# Beehive_sensor_PCB_Rev_2_0_Fixed.net
KiCad netlist of a schematic drawn in EAGLE
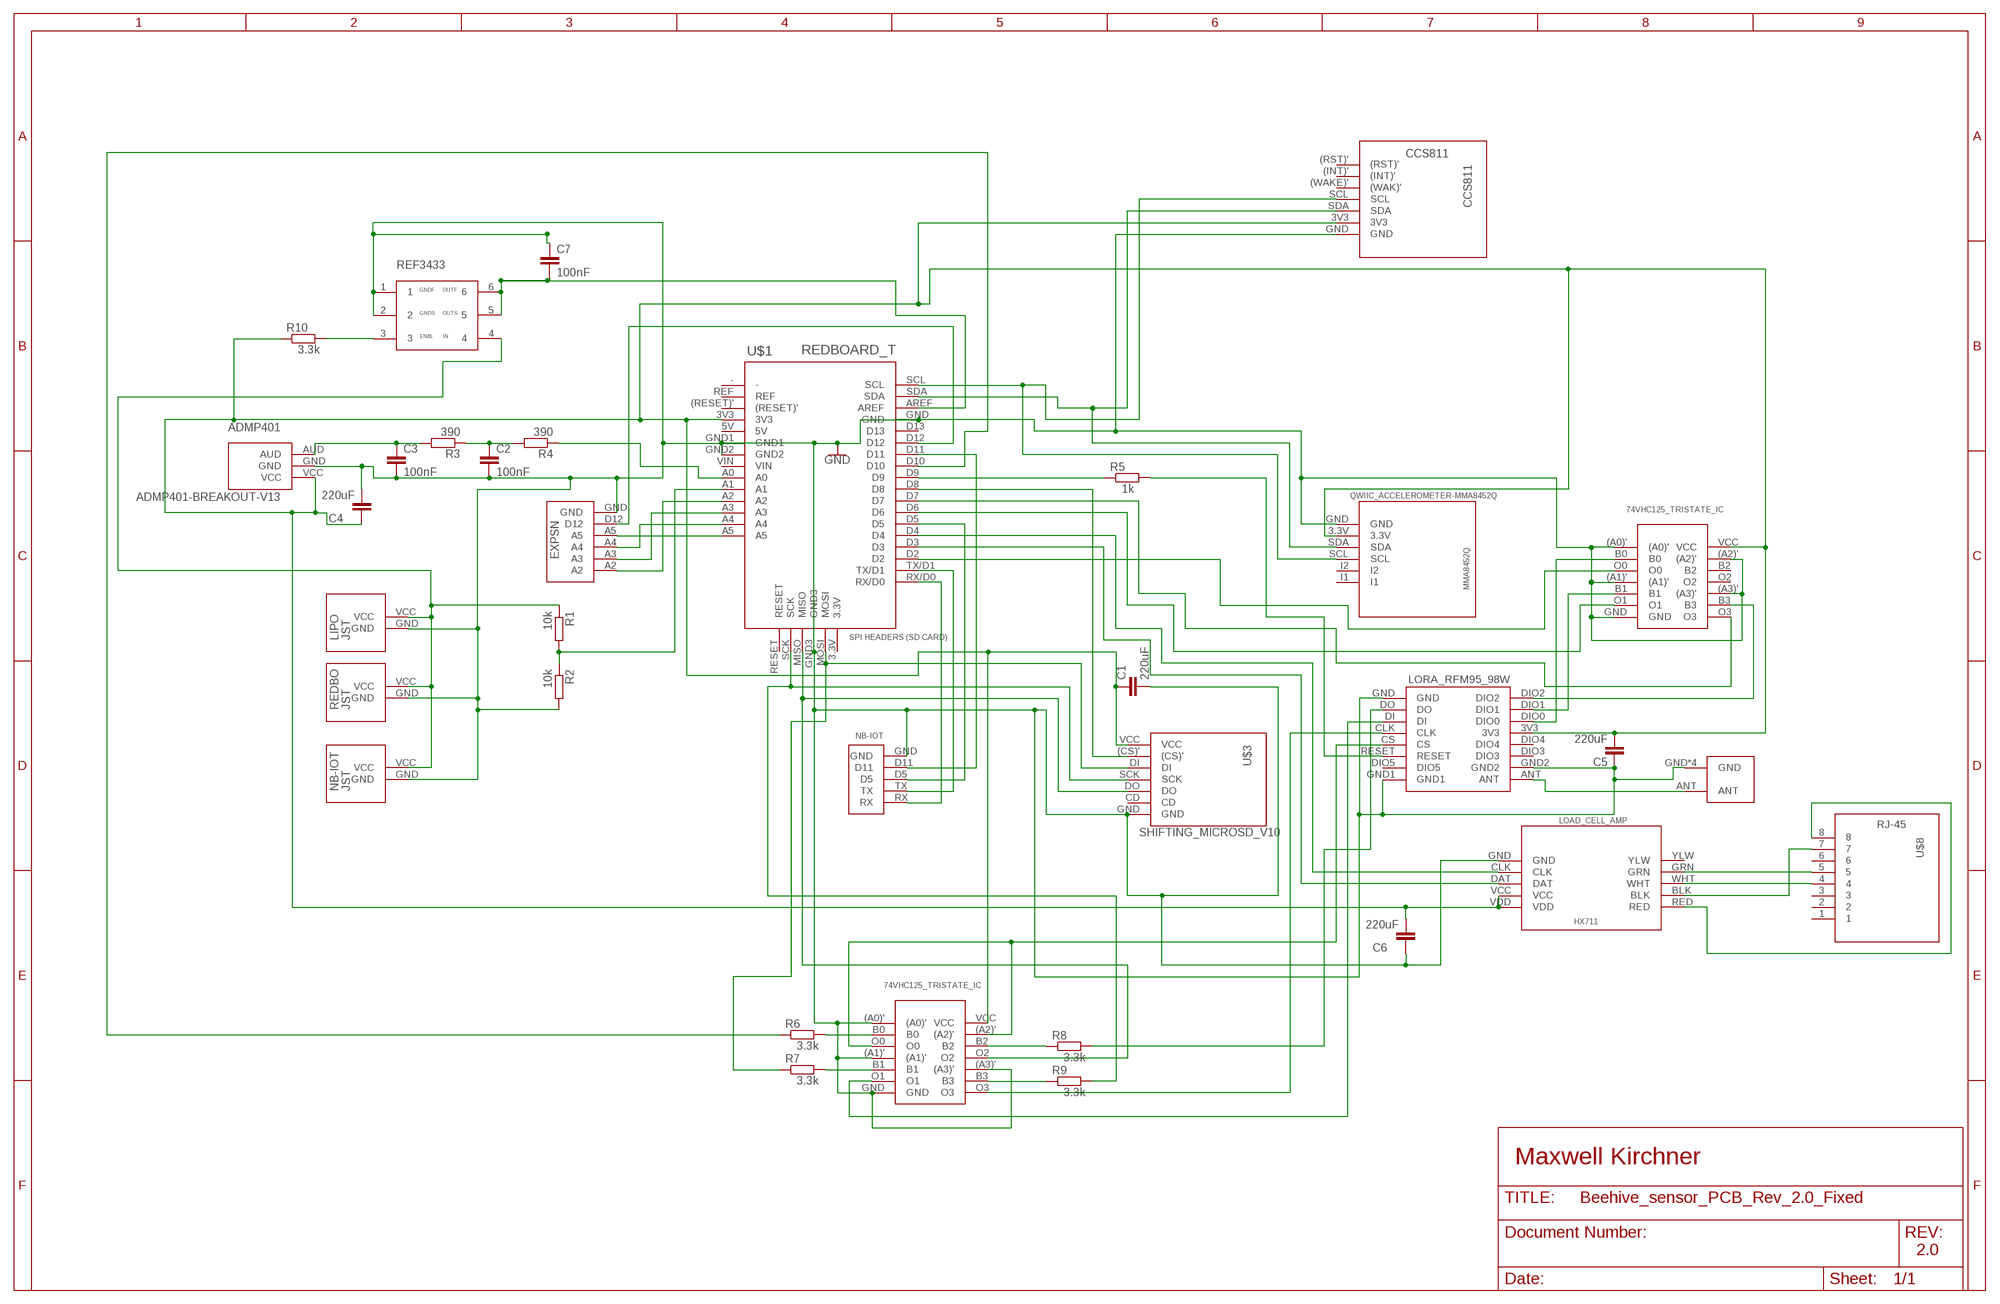
[diagram p0: schematic, sheet 1]

(export (version "E")
  (design (tool "Eeschema 10.0.6"))
  (components
    (comp (ref "ADMP401")
      (value "ADMP401-BREAKOUT-V13")
      (footprint "eagle-import:ADMP401-BREAKOUT-V13")
      (libsource (lib "eagle-import") (part "ADMP401-BREAKOUT-V13"))
    )
    (comp (ref "C1")
      (value "220uF")
      (footprint "eagle-import:C025-025X050")
      (libsource (lib "eagle-import") (part "C-EU025-025X050"))
    )
    (comp (ref "C2")
      (value "100nF")
      (footprint "eagle-import:C025-025X050")
      (libsource (lib "eagle-import") (part "C-EU025-025X050"))
    )
    (comp (ref "C3")
      (value "100nF")
      (footprint "eagle-import:C025-025X050")
      (libsource (lib "eagle-import") (part "C-EU025-025X050"))
    )
    (comp (ref "C4")
      (value "220uF")
      (footprint "eagle-import:C025-025X050")
      (libsource (lib "eagle-import") (part "C-EU025-025X050"))
    )
    (comp (ref "C5")
      (value "220uF")
      (footprint "eagle-import:C025-025X050")
      (libsource (lib "eagle-import") (part "C-EU025-025X050"))
    )
    (comp (ref "C6")
      (value "220uF")
      (footprint "eagle-import:C025-025X050")
      (libsource (lib "eagle-import") (part "C-EU025-025X050"))
    )
    (comp (ref "C7")
      (value "100nF")
      (footprint "eagle-import:C025-024X044")
      (libsource (lib "eagle-import") (part "C-EU025-024X044"))
    )
    (comp (ref "CCS811")
      (value "CCS811")
      (footprint "eagle-import:CCS811")
      (libsource (lib "eagle-import") (part "CCS811"))
    )
    (comp (ref "LIPO")
      (value "JST")
      (footprint "eagle-import:JST")
      (libsource (lib "eagle-import") (part "JST"))
    )
    (comp (ref "LOAD_CELL_AMP")
      (value "HX711")
      (footprint "eagle-import:HX711_LOAD_CELL_V11")
      (libsource (lib "eagle-import") (part "HX711"))
    )
    (comp (ref "MMA8452Q")
      (value "QWIIC_ACCELEROMETER-MMA8452Q")
      (footprint "eagle-import:QWIIC_ACCELEROMETER-MMA8452Q")
      (libsource (lib "eagle-import") (part "QWIIC_ACCELEROMETER-MMA8452Q"))
    )
    (comp (ref "NB-IOT")
      (value "JST")
      (footprint "eagle-import:JST")
      (libsource (lib "eagle-import") (part "JST"))
    )
    (comp (ref "R1")
      (value "10k")
      (footprint "eagle-import:0204_7")
      (libsource (lib "eagle-import") (part "R-EU_0204/7"))
    )
    (comp (ref "R2")
      (value "10k")
      (footprint "eagle-import:0204_7")
      (libsource (lib "eagle-import") (part "R-EU_0204/7"))
    )
    (comp (ref "R3")
      (value "390")
      (footprint "eagle-import:0204_7")
      (libsource (lib "eagle-import") (part "R-EU_0204/7"))
    )
    (comp (ref "R4")
      (value "390")
      (footprint "eagle-import:0204_7")
      (libsource (lib "eagle-import") (part "R-EU_0204/7"))
    )
    (comp (ref "R5")
      (value "1k")
      (footprint "eagle-import:0204_7")
      (libsource (lib "eagle-import") (part "R-EU_0204/7"))
    )
    (comp (ref "R6")
      (value "3.3k")
      (footprint "eagle-import:0204_7")
      (libsource (lib "eagle-import") (part "R-EU_0204/7"))
    )
    (comp (ref "R7")
      (value "3.3k")
      (footprint "eagle-import:0204_7")
      (libsource (lib "eagle-import") (part "R-EU_0204/7"))
    )
    (comp (ref "R8")
      (value "3.3k")
      (footprint "eagle-import:0204_7")
      (libsource (lib "eagle-import") (part "R-EU_0204/7"))
    )
    (comp (ref "R9")
      (value "3.3k")
      (footprint "eagle-import:0204_7")
      (libsource (lib "eagle-import") (part "R-EU_0204/7"))
    )
    (comp (ref "R10")
      (value "3.3k")
      (footprint "eagle-import:0204_7")
      (libsource (lib "eagle-import") (part "R-EU_0204/7"))
    )
    (comp (ref "REDBO")
      (value "JST")
      (footprint "eagle-import:JST")
      (libsource (lib "eagle-import") (part "JST"))
    )
    (comp (ref "U$1")
      (value "REDBOARD_T")
      (footprint "eagle-import:REDBOARD_T")
      (libsource (lib "eagle-import") (part "REDBOARD_T"))
    )
    (comp (ref "U$2")
      (value "LORA_RFM95_98W")
      (footprint "eagle-import:RFM95_98W")
      (libsource (lib "eagle-import") (part "LORA_RFM95_98W"))
    )
    (comp (ref "U$3")
      (value "SHIFTING_MICROSD_V10")
      (footprint "eagle-import:SHIFTING_MICROSD_V10")
      (libsource (lib "eagle-import") (part "SHIFTING_MICROSD_V10"))
    )
    (comp (ref "U$8")
      (value "RJ-45")
      (footprint "eagle-import:RJ-45")
      (libsource (lib "eagle-import") (part "RJ-45"))
    )
    (comp (ref "U$9")
      (value "74VHC125_TRISTATE_IC")
      (footprint "eagle-import:74VHC125")
      (libsource (lib "eagle-import") (part "74VHC125_TRISTATE_IC"))
    )
    (comp (ref "U$10")
      (value "ANT")
      (footprint "eagle-import:ANT")
      (libsource (lib "eagle-import") (part "ANT"))
    )
    (comp (ref "U$11")
      (value "NB-IOT")
      (footprint "eagle-import:NB-IOT")
      (libsource (lib "eagle-import") (part "NB-IOT"))
    )
    (comp (ref "U$12")
      (value "EXPSN")
      (footprint "eagle-import:EXPSN")
      (libsource (lib "eagle-import") (part "EXPSN"))
    )
    (comp (ref "U$13")
      (value "REF3433")
      (footprint "eagle-import:REF3433")
      (libsource (lib "eagle-import") (part "REF3433"))
    )
    (comp (ref "U$14")
      (value "74VHC125_TRISTATE_IC")
      (footprint "eagle-import:74VHC125")
      (libsource (lib "eagle-import") (part "74VHC125_TRISTATE_IC"))
    )
  )
  (nets
    (net (code "1") (name "GND") (class "Default")
      (node (ref "ADMP401") (pin "GND") (pinfunction "GND_GND") (pintype "bidirectional"))
      (node (ref "C1") (pin "2") (pinfunction "2_2") (pintype "passive"))
      (node (ref "C2") (pin "2") (pinfunction "2_2") (pintype "passive"))
      (node (ref "C3") (pin "2") (pinfunction "2_2") (pintype "passive"))
      (node (ref "C4") (pin "2") (pinfunction "2_2") (pintype "passive"))
      (node (ref "C5") (pin "1") (pinfunction "1_1") (pintype "passive"))
      (node (ref "C6") (pin "1") (pinfunction "1_1") (pintype "passive"))
      (node (ref "C7") (pin "1") (pinfunction "1_1") (pintype "passive"))
      (node (ref "CCS811") (pin "GND") (pinfunction "GND_GND") (pintype "bidirectional"))
      (node (ref "LIPO") (pin "GND") (pinfunction "GND_GND") (pintype "bidirectional"))
      (node (ref "LOAD_CELL_AMP") (pin "GND") (pinfunction "GND_GND") (pintype "bidirectional"))
      (node (ref "MMA8452Q") (pin "GND") (pinfunction "GND_GND") (pintype "bidirectional"))
      (node (ref "NB-IOT") (pin "GND") (pinfunction "GND_GND") (pintype "bidirectional"))
      (node (ref "R2") (pin "2") (pinfunction "2_2") (pintype "passive"))
      (node (ref "REDBO") (pin "GND") (pinfunction "GND_GND") (pintype "bidirectional"))
      (node (ref "U$1") (pin "GND") (pinfunction "GND_GND") (pintype "bidirectional"))
      (node (ref "U$1") (pin "GND1") (pinfunction "GND1_GND1") (pintype "bidirectional"))
      (node (ref "U$1") (pin "GND2") (pinfunction "GND2_GND2") (pintype "bidirectional"))
      (node (ref "U$1") (pin "GND3") (pinfunction "GND3_GND3") (pintype "bidirectional"))
      (node (ref "U$10") (pin "GND") (pinfunction "GND_GND") (pintype "bidirectional"))
      (node (ref "U$10") (pin "GND1") (pinfunction "GND_GND1") (pintype "bidirectional"))
      (node (ref "U$10") (pin "GND2") (pinfunction "GND_GND2") (pintype "bidirectional"))
      (node (ref "U$10") (pin "GND3") (pinfunction "GND_GND3") (pintype "bidirectional"))
      (node (ref "U$11") (pin "GND") (pinfunction "GND_GND") (pintype "bidirectional"))
      (node (ref "U$12") (pin "GND") (pinfunction "GND_GND") (pintype "bidirectional"))
      (node (ref "U$13") (pin "1") (pinfunction "1_1") (pintype "bidirectional"))
      (node (ref "U$13") (pin "2") (pinfunction "2_2") (pintype "bidirectional"))
      (node (ref "U$14") (pin "(A0)'") (pinfunction "(A0)'_(A0)'") (pintype "bidirectional"))
      (node (ref "U$14") (pin "(A1)'") (pinfunction "(A1)'_(A1)'") (pintype "bidirectional"))
      (node (ref "U$14") (pin "(A2)'") (pinfunction "(A2)'_(A2)'") (pintype "bidirectional"))
      (node (ref "U$14") (pin "(A3)'") (pinfunction "(A3)'_(A3)'") (pintype "bidirectional"))
      (node (ref "U$14") (pin "GND") (pinfunction "GND_GND") (pintype "bidirectional"))
      (node (ref "U$2") (pin "GND") (pinfunction "GND_GND") (pintype "bidirectional"))
      (node (ref "U$2") (pin "GND1") (pinfunction "GND1_GND1") (pintype "bidirectional"))
      (node (ref "U$2") (pin "GND2") (pinfunction "GND2_GND2") (pintype "bidirectional"))
      (node (ref "U$3") (pin "GND") (pinfunction "GND_GND") (pintype "bidirectional"))
      (node (ref "U$9") (pin "(A0)'") (pinfunction "(A0)'_(A0)'") (pintype "bidirectional"))
      (node (ref "U$9") (pin "(A1)'") (pinfunction "(A1)'_(A1)'") (pintype "bidirectional"))
      (node (ref "U$9") (pin "(A3)'") (pinfunction "(A3)'_(A3)'") (pintype "bidirectional"))
      (node (ref "U$9") (pin "GND") (pinfunction "GND_GND") (pintype "bidirectional"))
    )
    (net (code "2") (name "Net-(ADMP401-PadAUD)") (class "Default")
      (node (ref "ADMP401") (pin "AUD") (pinfunction "AUD_AUD") (pintype "bidirectional"))
      (node (ref "C3") (pin "1") (pinfunction "1_1") (pintype "passive"))
      (node (ref "R3") (pin "2") (pinfunction "2_2") (pintype "passive"))
    )
    (net (code "3") (name "Net-(ADMP401-PadVCC)") (class "Default")
      (node (ref "ADMP401") (pin "VCC") (pinfunction "VCC_VCC") (pintype "bidirectional"))
      (node (ref "C1") (pin "1") (pinfunction "1_1") (pintype "passive"))
      (node (ref "C4") (pin "1") (pinfunction "1_1") (pintype "passive"))
      (node (ref "C5") (pin "2") (pinfunction "2_2") (pintype "passive"))
      (node (ref "C6") (pin "2") (pinfunction "2_2") (pintype "passive"))
      (node (ref "CCS811") (pin "3V3") (pinfunction "3V3_3V3") (pintype "bidirectional"))
      (node (ref "LOAD_CELL_AMP") (pin "VCC") (pinfunction "VCC_VCC") (pintype "bidirectional"))
      (node (ref "LOAD_CELL_AMP") (pin "VDD") (pinfunction "VDD_VDD") (pintype "bidirectional"))
      (node (ref "MMA8452Q") (pin "3.3V") (pinfunction "3.3V_3.3V") (pintype "bidirectional"))
      (node (ref "R10") (pin "1") (pinfunction "1_1") (pintype "passive"))
      (node (ref "U$1") (pin "3V3") (pinfunction "3V3_3V3") (pintype "bidirectional"))
      (node (ref "U$14") (pin "VCC") (pinfunction "VCC_VCC") (pintype "bidirectional"))
      (node (ref "U$2") (pin "3V3") (pinfunction "3V3_3V3") (pintype "bidirectional"))
      (node (ref "U$3") (pin "VCC") (pinfunction "VCC_VCC") (pintype "bidirectional"))
      (node (ref "U$9") (pin "VCC") (pinfunction "VCC_VCC") (pintype "bidirectional"))
    )
    (net (code "4") (name "Net-(C2-Pad1)") (class "Default")
      (node (ref "C2") (pin "1") (pinfunction "1_1") (pintype "passive"))
      (node (ref "R3") (pin "1") (pinfunction "1_1") (pintype "passive"))
      (node (ref "R4") (pin "2") (pinfunction "2_2") (pintype "passive"))
    )
    (net (code "5") (name "Net-(C7-Pad2)") (class "Default")
      (node (ref "C7") (pin "2") (pinfunction "2_2") (pintype "passive"))
      (node (ref "U$1") (pin "AREF") (pinfunction "AREF_AREF") (pintype "bidirectional"))
      (node (ref "U$13") (pin "5") (pinfunction "5_5") (pintype "bidirectional"))
      (node (ref "U$13") (pin "6") (pinfunction "6_6") (pintype "bidirectional"))
    )
    (net (code "6") (name "Net-(CCS811-PadSCL)") (class "Default")
      (node (ref "CCS811") (pin "SCL") (pinfunction "SCL_SCL") (pintype "bidirectional"))
      (node (ref "MMA8452Q") (pin "SCL") (pinfunction "SCL_SCL") (pintype "bidirectional"))
      (node (ref "U$1") (pin "SCL") (pinfunction "SCL_SCL") (pintype "bidirectional"))
    )
    (net (code "7") (name "Net-(CCS811-PadSDA)") (class "Default")
      (node (ref "CCS811") (pin "SDA") (pinfunction "SDA_SDA") (pintype "bidirectional"))
      (node (ref "MMA8452Q") (pin "SDA") (pinfunction "SDA_SDA") (pintype "bidirectional"))
      (node (ref "U$1") (pin "SDA") (pinfunction "SDA_SDA") (pintype "bidirectional"))
    )
    (net (code "8") (name "Net-(LIPO-PadVCC)") (class "Default")
      (node (ref "LIPO") (pin "VCC") (pinfunction "VCC_VCC") (pintype "bidirectional"))
      (node (ref "NB-IOT") (pin "VCC") (pinfunction "VCC_VCC") (pintype "bidirectional"))
      (node (ref "R1") (pin "1") (pinfunction "1_1") (pintype "passive"))
      (node (ref "REDBO") (pin "VCC") (pinfunction "VCC_VCC") (pintype "bidirectional"))
      (node (ref "U$13") (pin "4") (pinfunction "4_4") (pintype "bidirectional"))
    )
    (net (code "9") (name "Net-(LOAD_CELL_AMP-PadBLK)") (class "Default")
      (node (ref "LOAD_CELL_AMP") (pin "BLK") (pinfunction "BLK_BLK") (pintype "bidirectional"))
      (node (ref "U$8") (pin "7") (pinfunction "7_7") (pintype "bidirectional"))
    )
    (net (code "10") (name "Net-(LOAD_CELL_AMP-PadCLK)") (class "Default")
      (node (ref "LOAD_CELL_AMP") (pin "CLK") (pinfunction "CLK_CLK") (pintype "bidirectional"))
      (node (ref "U$1") (pin "D4") (pinfunction "D4_D4") (pintype "bidirectional"))
    )
    (net (code "11") (name "Net-(LOAD_CELL_AMP-PadDAT)") (class "Default")
      (node (ref "LOAD_CELL_AMP") (pin "DAT") (pinfunction "DAT_DAT") (pintype "bidirectional"))
      (node (ref "U$1") (pin "D3") (pinfunction "D3_D3") (pintype "bidirectional"))
    )
    (net (code "12") (name "Net-(LOAD_CELL_AMP-PadGRN)") (class "Default")
      (node (ref "LOAD_CELL_AMP") (pin "GRN") (pinfunction "GRN_GRN") (pintype "bidirectional"))
      (node (ref "U$8") (pin "5") (pinfunction "5_5") (pintype "bidirectional"))
    )
    (net (code "13") (name "Net-(LOAD_CELL_AMP-PadRED)") (class "Default")
      (node (ref "LOAD_CELL_AMP") (pin "RED") (pinfunction "RED_RED") (pintype "bidirectional"))
      (node (ref "U$8") (pin "8") (pinfunction "8_8") (pintype "bidirectional"))
    )
    (net (code "14") (name "Net-(LOAD_CELL_AMP-PadWHT)") (class "Default")
      (node (ref "LOAD_CELL_AMP") (pin "WHT") (pinfunction "WHT_WHT") (pintype "bidirectional"))
      (node (ref "U$8") (pin "4") (pinfunction "4_4") (pintype "bidirectional"))
    )
    (net (code "15") (name "Net-(R1-Pad2)") (class "Default")
      (node (ref "R1") (pin "2") (pinfunction "2_2") (pintype "passive"))
      (node (ref "R2") (pin "1") (pinfunction "1_1") (pintype "passive"))
      (node (ref "U$1") (pin "A1") (pinfunction "A1_A1") (pintype "bidirectional"))
    )
    (net (code "16") (name "Net-(R4-Pad1)") (class "Default")
      (node (ref "R4") (pin "1") (pinfunction "1_1") (pintype "passive"))
      (node (ref "U$1") (pin "A0") (pinfunction "A0_A0") (pintype "bidirectional"))
    )
    (net (code "17") (name "Net-(R5-Pad1)") (class "Default")
      (node (ref "R5") (pin "1") (pinfunction "1_1") (pintype "passive"))
      (node (ref "U$1") (pin "D9") (pinfunction "D9_D9") (pintype "bidirectional"))
    )
    (net (code "18") (name "Net-(R5-Pad2)") (class "Default")
      (node (ref "R5") (pin "2") (pinfunction "2_2") (pintype "passive"))
      (node (ref "U$2") (pin "RESET") (pinfunction "RESET_RESET") (pintype "bidirectional"))
    )
    (net (code "19") (name "Net-(R6-Pad1)") (class "Default")
      (node (ref "R6") (pin "1") (pinfunction "1_1") (pintype "passive"))
      (node (ref "U$1") (pin "D10") (pinfunction "D10_D10") (pintype "bidirectional"))
    )
    (net (code "20") (name "Net-(R6-Pad2)") (class "Default")
      (node (ref "R6") (pin "2") (pinfunction "2_2") (pintype "passive"))
      (node (ref "U$9") (pin "B0") (pinfunction "B0_B0") (pintype "bidirectional"))
    )
    (net (code "21") (name "Net-(R7-Pad1)") (class "Default")
      (node (ref "R7") (pin "1") (pinfunction "1_1") (pintype "passive"))
      (node (ref "U$1") (pin "MOSI") (pinfunction "MOSI_MOSI") (pintype "bidirectional"))
      (node (ref "U$3") (pin "DI") (pinfunction "DI_DI") (pintype "bidirectional"))
    )
    (net (code "22") (name "Net-(R7-Pad2)") (class "Default")
      (node (ref "R7") (pin "2") (pinfunction "2_2") (pintype "passive"))
      (node (ref "U$9") (pin "B1") (pinfunction "B1_B1") (pintype "bidirectional"))
    )
    (net (code "23") (name "Net-(R8-Pad1)") (class "Default")
      (node (ref "R8") (pin "1") (pinfunction "1_1") (pintype "passive"))
      (node (ref "U$9") (pin "B2") (pinfunction "B2_B2") (pintype "bidirectional"))
    )
    (net (code "24") (name "Net-(R8-Pad2)") (class "Default")
      (node (ref "R8") (pin "2") (pinfunction "2_2") (pintype "passive"))
      (node (ref "U$2") (pin "DO") (pinfunction "DO_DO") (pintype "bidirectional"))
    )
    (net (code "25") (name "Net-(R9-Pad1)") (class "Default")
      (node (ref "R9") (pin "1") (pinfunction "1_1") (pintype "passive"))
      (node (ref "U$9") (pin "B3") (pinfunction "B3_B3") (pintype "bidirectional"))
    )
    (net (code "26") (name "Net-(R9-Pad2)") (class "Default")
      (node (ref "R9") (pin "2") (pinfunction "2_2") (pintype "passive"))
      (node (ref "U$1") (pin "SCK") (pinfunction "SCK_SCK") (pintype "bidirectional"))
      (node (ref "U$3") (pin "SCK") (pinfunction "SCK_SCK") (pintype "bidirectional"))
    )
    (net (code "27") (name "Net-(R10-Pad2)") (class "Default")
      (node (ref "R10") (pin "2") (pinfunction "2_2") (pintype "passive"))
      (node (ref "U$13") (pin "3") (pinfunction "3_3") (pintype "bidirectional"))
    )
    (net (code "28") (name "Net-(U$1-PadA2)") (class "Default")
      (node (ref "U$1") (pin "A2") (pinfunction "A2_A2") (pintype "bidirectional"))
      (node (ref "U$12") (pin "A2") (pinfunction "A2_A2") (pintype "bidirectional"))
    )
    (net (code "29") (name "Net-(U$1-PadA3)") (class "Default")
      (node (ref "U$1") (pin "A3") (pinfunction "A3_A3") (pintype "bidirectional"))
      (node (ref "U$12") (pin "A3") (pinfunction "A3_A3") (pintype "bidirectional"))
    )
    (net (code "30") (name "Net-(U$1-PadA4)") (class "Default")
      (node (ref "U$1") (pin "A4") (pinfunction "A4_A4") (pintype "bidirectional"))
      (node (ref "U$12") (pin "A4") (pinfunction "A4_A4") (pintype "bidirectional"))
    )
    (net (code "31") (name "Net-(U$1-PadA5)") (class "Default")
      (node (ref "U$1") (pin "A5") (pinfunction "A5_A5") (pintype "bidirectional"))
      (node (ref "U$12") (pin "A5") (pinfunction "A5_A5") (pintype "bidirectional"))
    )
    (net (code "32") (name "Net-(U$1-PadD2)") (class "Default")
      (node (ref "U$1") (pin "D2") (pinfunction "D2_D2") (pintype "bidirectional"))
      (node (ref "U$14") (pin "O0") (pinfunction "O0_O0") (pintype "bidirectional"))
    )
    (net (code "33") (name "Net-(U$1-PadD5)") (class "Default")
      (node (ref "U$1") (pin "D5") (pinfunction "D5_D5") (pintype "bidirectional"))
      (node (ref "U$11") (pin "D5") (pinfunction "D5_D5") (pintype "bidirectional"))
    )
    (net (code "34") (name "Net-(U$1-PadD6)") (class "Default")
      (node (ref "U$1") (pin "D6") (pinfunction "D6_D6") (pintype "bidirectional"))
      (node (ref "U$14") (pin "O1") (pinfunction "O1_O1") (pintype "bidirectional"))
    )
    (net (code "35") (name "Net-(U$1-PadD7)") (class "Default")
      (node (ref "U$1") (pin "D7") (pinfunction "D7_D7") (pintype "bidirectional"))
      (node (ref "U$14") (pin "O3") (pinfunction "O3_O3") (pintype "bidirectional"))
    )
    (net (code "36") (name "Net-(U$1-PadD8)") (class "Default")
      (node (ref "U$1") (pin "D8") (pinfunction "D8_D8") (pintype "bidirectional"))
      (node (ref "U$3") (pin "(CS)'") (pinfunction "(CS)'_(CS)'") (pintype "bidirectional"))
    )
    (net (code "37") (name "Net-(U$1-PadD11)") (class "Default")
      (node (ref "U$1") (pin "D11") (pinfunction "D11_D11") (pintype "bidirectional"))
      (node (ref "U$11") (pin "D11") (pinfunction "D11_D11") (pintype "bidirectional"))
    )
    (net (code "38") (name "Net-(U$1-PadD12)") (class "Default")
      (node (ref "U$1") (pin "D12") (pinfunction "D12_D12") (pintype "bidirectional"))
      (node (ref "U$12") (pin "D12") (pinfunction "D12_D12") (pintype "bidirectional"))
    )
    (net (code "39") (name "Net-(U$1-PadMISO)") (class "Default")
      (node (ref "U$1") (pin "MISO") (pinfunction "MISO_MISO") (pintype "bidirectional"))
      (node (ref "U$3") (pin "DO") (pinfunction "DO_DO") (pintype "bidirectional"))
      (node (ref "U$9") (pin "O2") (pinfunction "O2_O2") (pintype "bidirectional"))
    )
    (net (code "40") (name "Net-(U$1-PadRX{slash}D0)") (class "Default")
      (node (ref "U$1") (pin "RX/D0") (pinfunction "RX/D0_RX/D0") (pintype "bidirectional"))
      (node (ref "U$11") (pin "RX") (pinfunction "RX_RX") (pintype "bidirectional"))
    )
    (net (code "41") (name "Net-(U$1-PadTX{slash}D1)") (class "Default")
      (node (ref "U$1") (pin "TX/D1") (pinfunction "TX/D1_TX/D1") (pintype "bidirectional"))
      (node (ref "U$11") (pin "TX") (pinfunction "TX_TX") (pintype "bidirectional"))
    )
    (net (code "42") (name "Net-(U$2-PadCLK)") (class "Default")
      (node (ref "U$2") (pin "CLK") (pinfunction "CLK_CLK") (pintype "bidirectional"))
      (node (ref "U$9") (pin "O3") (pinfunction "O3_O3") (pintype "bidirectional"))
    )
    (net (code "43") (name "Net-(U$2-PadCS)") (class "Default")
      (node (ref "U$2") (pin "CS") (pinfunction "CS_CS") (pintype "bidirectional"))
      (node (ref "U$9") (pin "(A2)'") (pinfunction "(A2)'_(A2)'") (pintype "bidirectional"))
      (node (ref "U$9") (pin "O0") (pinfunction "O0_O0") (pintype "bidirectional"))
    )
    (net (code "44") (name "Net-(U$2-PadDI)") (class "Default")
      (node (ref "U$2") (pin "DI") (pinfunction "DI_DI") (pintype "bidirectional"))
      (node (ref "U$9") (pin "O1") (pinfunction "O1_O1") (pintype "bidirectional"))
    )
    (net (code "45") (name "Net-(U$10-PadANT)") (class "Default")
      (node (ref "U$10") (pin "ANT") (pinfunction "ANT_ANT") (pintype "bidirectional"))
      (node (ref "U$2") (pin "ANT") (pinfunction "ANT_ANT") (pintype "bidirectional"))
    )
    (net (code "46") (name "Net-(U$14-PadB0)") (class "Default")
      (node (ref "U$14") (pin "B0") (pinfunction "B0_B0") (pintype "bidirectional"))
      (node (ref "U$2") (pin "DIO0") (pinfunction "DIO0_DIO0") (pintype "bidirectional"))
    )
    (net (code "47") (name "Net-(U$14-PadB1)") (class "Default")
      (node (ref "U$14") (pin "B1") (pinfunction "B1_B1") (pintype "bidirectional"))
      (node (ref "U$2") (pin "DIO1") (pinfunction "DIO1_DIO1") (pintype "bidirectional"))
    )
    (net (code "48") (name "Net-(U$14-PadB3)") (class "Default")
      (node (ref "U$14") (pin "B3") (pinfunction "B3_B3") (pintype "bidirectional"))
      (node (ref "U$2") (pin "DIO2") (pinfunction "DIO2_DIO2") (pintype "bidirectional"))
    )
    (net (code "49") (name "unconnected-(CCS811-(WAK)'-Pad(WAKE)')") (class "Default")
      (node (ref "CCS811") (pin "(WAKE)'") (pinfunction "(WAK)'_(WAKE)'") (pintype "bidirectional"))
    )
    (net (code "50") (name "unconnected-(CCS811-Pad(INT)')") (class "Default")
      (node (ref "CCS811") (pin "(INT)'") (pinfunction "(INT)'_(INT)'") (pintype "bidirectional"))
    )
    (net (code "51") (name "unconnected-(CCS811-Pad(RST)')") (class "Default")
      (node (ref "CCS811") (pin "(RST)'") (pinfunction "(RST)'_(RST)'") (pintype "bidirectional"))
    )
    (net (code "52") (name "unconnected-(LOAD_CELL_AMP-PadYLW)") (class "Default")
      (node (ref "LOAD_CELL_AMP") (pin "YLW") (pinfunction "YLW_YLW") (pintype "bidirectional"))
    )
    (net (code "53") (name "unconnected-(MMA8452Q-PadI1)") (class "Default")
      (node (ref "MMA8452Q") (pin "I1") (pinfunction "I1_I1") (pintype "bidirectional"))
    )
    (net (code "54") (name "unconnected-(MMA8452Q-PadI2)") (class "Default")
      (node (ref "MMA8452Q") (pin "I2") (pinfunction "I2_I2") (pintype "bidirectional"))
    )
    (net (code "55") (name "unconnected-(U$1-Pad(RESET)')") (class "Default")
      (node (ref "U$1") (pin "(RESET)'") (pinfunction "(RESET)'_(RESET)'") (pintype "bidirectional"))
    )
    (net (code "56") (name "unconnected-(U$1-Pad-)") (class "Default")
      (node (ref "U$1") (pin "-") (pinfunction "-_-") (pintype "bidirectional"))
    )
    (net (code "57") (name "unconnected-(U$1-Pad3.3V)") (class "Default")
      (node (ref "U$1") (pin "3.3V") (pinfunction "3.3V_3.3V") (pintype "bidirectional"))
    )
    (net (code "58") (name "unconnected-(U$1-Pad5V)") (class "Default")
      (node (ref "U$1") (pin "5V") (pinfunction "5V_5V") (pintype "bidirectional"))
    )
    (net (code "59") (name "unconnected-(U$1-PadD13)") (class "Default")
      (node (ref "U$1") (pin "D13") (pinfunction "D13_D13") (pintype "bidirectional"))
    )
    (net (code "60") (name "unconnected-(U$1-PadREF)") (class "Default")
      (node (ref "U$1") (pin "REF") (pinfunction "REF_REF") (pintype "bidirectional"))
    )
    (net (code "61") (name "unconnected-(U$1-PadRESET)") (class "Default")
      (node (ref "U$1") (pin "RESET") (pinfunction "RESET_RESET") (pintype "bidirectional"))
    )
    (net (code "62") (name "unconnected-(U$1-PadVIN)") (class "Default")
      (node (ref "U$1") (pin "VIN") (pinfunction "VIN_VIN") (pintype "bidirectional"))
    )
    (net (code "63") (name "unconnected-(U$2-PadDIO3)") (class "Default")
      (node (ref "U$2") (pin "DIO3") (pinfunction "DIO3_DIO3") (pintype "bidirectional"))
    )
    (net (code "64") (name "unconnected-(U$2-PadDIO4)") (class "Default")
      (node (ref "U$2") (pin "DIO4") (pinfunction "DIO4_DIO4") (pintype "bidirectional"))
    )
    (net (code "65") (name "unconnected-(U$2-PadDIO5)") (class "Default")
      (node (ref "U$2") (pin "DIO5") (pinfunction "DIO5_DIO5") (pintype "bidirectional"))
    )
    (net (code "66") (name "unconnected-(U$3-PadCD)") (class "Default")
      (node (ref "U$3") (pin "CD") (pinfunction "CD_CD") (pintype "bidirectional"))
    )
    (net (code "67") (name "unconnected-(U$8-Pad1)") (class "Default")
      (node (ref "U$8") (pin "1") (pinfunction "1_1") (pintype "bidirectional"))
    )
    (net (code "68") (name "unconnected-(U$8-Pad2)") (class "Default")
      (node (ref "U$8") (pin "2") (pinfunction "2_2") (pintype "bidirectional"))
    )
    (net (code "69") (name "unconnected-(U$8-Pad3)") (class "Default")
      (node (ref "U$8") (pin "3") (pinfunction "3_3") (pintype "bidirectional"))
    )
    (net (code "70") (name "unconnected-(U$8-Pad6)") (class "Default")
      (node (ref "U$8") (pin "6") (pinfunction "6_6") (pintype "bidirectional"))
    )
    (net (code "71") (name "unconnected-(U$14-PadB2)") (class "Default")
      (node (ref "U$14") (pin "B2") (pinfunction "B2_B2") (pintype "bidirectional"))
    )
    (net (code "72") (name "unconnected-(U$14-PadO2)") (class "Default")
      (node (ref "U$14") (pin "O2") (pinfunction "O2_O2") (pintype "bidirectional"))
    )
  )
)
